# vias.net
KiCad netlist of a schematic drawn in Altium Designer
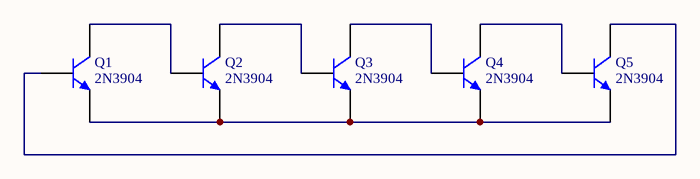
[diagram p0: vias.SchDoc]

(export (version "E")
  (design (tool "Eeschema 10.0.6"))
  (components
    (comp (ref "Q1")
      (value "2N3904")
      (footprint "TO-92A")
      (description "NPN General Purpose Amplifier")
      (fields (field (name "PUBLISHER") "Altium Limited"))
      (libsource (lib "Miscellaneous Devices") (part "2N3904"))
    )
    (comp (ref "Q2")
      (value "2N3904")
      (footprint "TO-92A")
      (description "NPN General Purpose Amplifier")
      (fields (field (name "PUBLISHER") "Altium Limited"))
      (libsource (lib "Miscellaneous Devices") (part "2N3904"))
    )
    (comp (ref "Q3")
      (value "2N3904")
      (footprint "TO-92A")
      (description "NPN General Purpose Amplifier")
      (fields (field (name "PUBLISHER") "Altium Limited"))
      (libsource (lib "Miscellaneous Devices") (part "2N3904"))
    )
    (comp (ref "Q4")
      (value "2N3904")
      (footprint "TO-92A")
      (description "NPN General Purpose Amplifier")
      (fields (field (name "PUBLISHER") "Altium Limited"))
      (libsource (lib "Miscellaneous Devices") (part "2N3904"))
    )
    (comp (ref "Q5")
      (value "2N3904")
      (footprint "TO-92A")
      (description "NPN General Purpose Amplifier")
      (fields (field (name "PUBLISHER") "Altium Limited"))
      (libsource (lib "Miscellaneous Devices") (part "2N3904"))
    )
  )
  (nets
    (net (code "1") (name "Net-(Q1-B)") (class "Default")
      (node (ref "Q1") (pin "2") (pinfunction "B_2") (pintype "passive"))
      (node (ref "Q5") (pin "3") (pinfunction "C_3") (pintype "passive"))
    )
    (net (code "2") (name "Net-(Q1-C)") (class "Default")
      (node (ref "Q1") (pin "3") (pinfunction "C_3") (pintype "passive"))
      (node (ref "Q2") (pin "2") (pinfunction "B_2") (pintype "passive"))
    )
    (net (code "3") (name "Net-(Q1-E)") (class "Default")
      (node (ref "Q1") (pin "1") (pinfunction "E_1") (pintype "passive"))
      (node (ref "Q2") (pin "1") (pinfunction "E_1") (pintype "passive"))
      (node (ref "Q3") (pin "1") (pinfunction "E_1") (pintype "passive"))
      (node (ref "Q4") (pin "1") (pinfunction "E_1") (pintype "passive"))
      (node (ref "Q5") (pin "1") (pinfunction "E_1") (pintype "passive"))
    )
    (net (code "4") (name "Net-(Q2-C)") (class "Default")
      (node (ref "Q2") (pin "3") (pinfunction "C_3") (pintype "passive"))
      (node (ref "Q3") (pin "2") (pinfunction "B_2") (pintype "passive"))
    )
    (net (code "5") (name "Net-(Q3-C)") (class "Default")
      (node (ref "Q3") (pin "3") (pinfunction "C_3") (pintype "passive"))
      (node (ref "Q4") (pin "2") (pinfunction "B_2") (pintype "passive"))
    )
    (net (code "6") (name "Net-(Q4-C)") (class "Default")
      (node (ref "Q4") (pin "3") (pinfunction "C_3") (pintype "passive"))
      (node (ref "Q5") (pin "2") (pinfunction "B_2") (pintype "passive"))
    )
  )
)
